# untitled.net
KiCad netlist of a schematic drawn in EAGLE
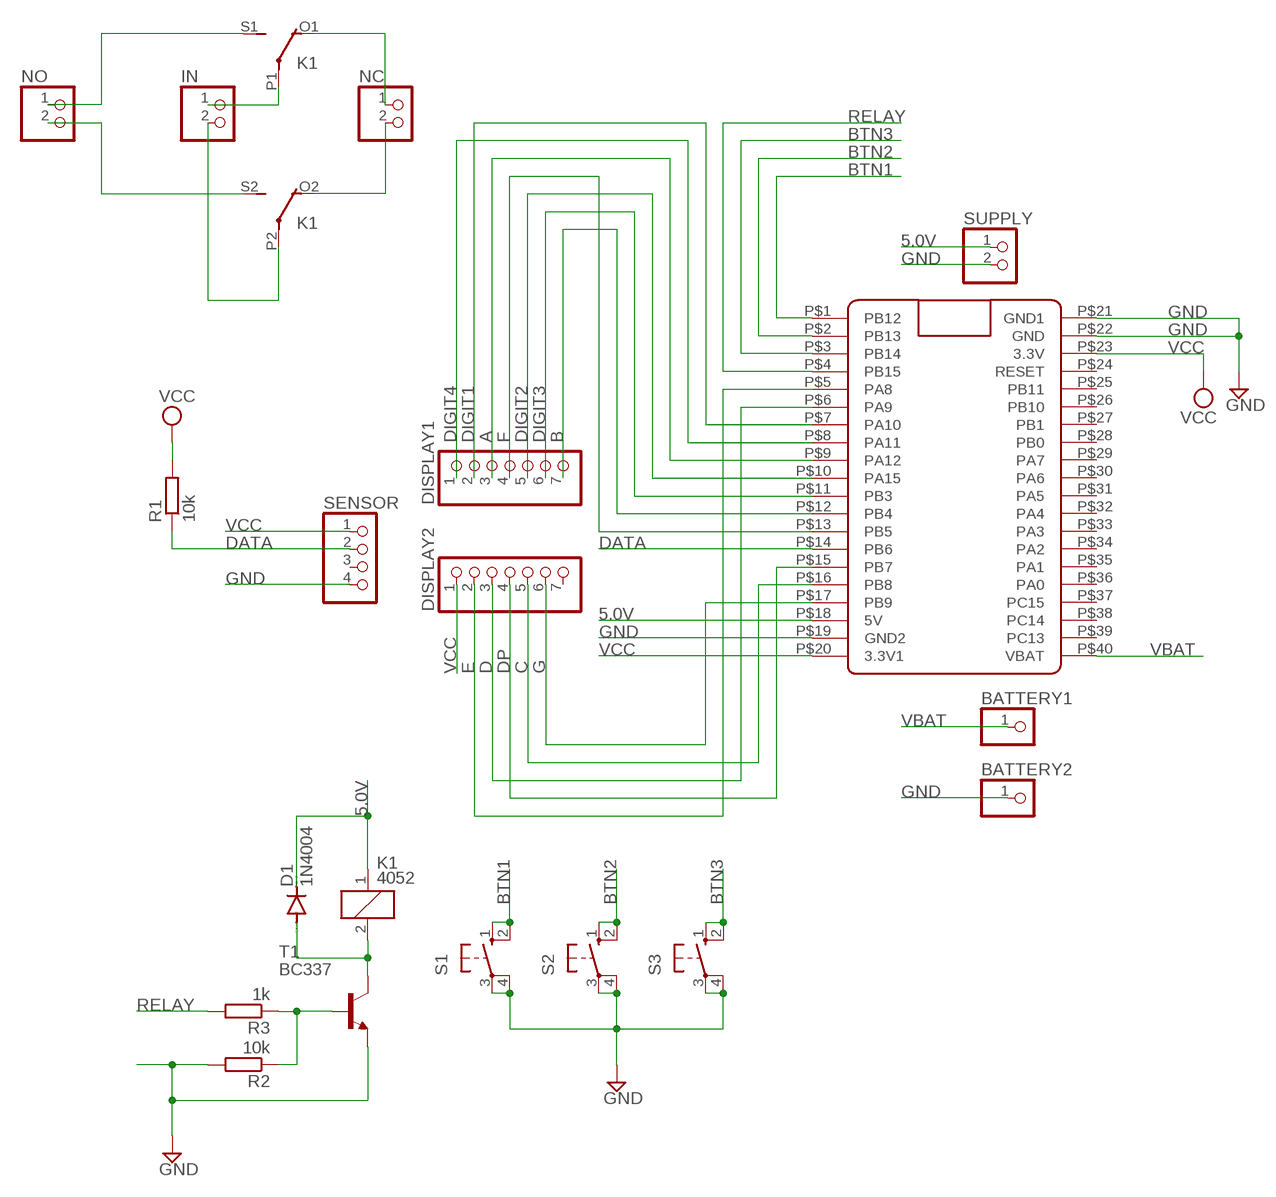
[diagram p0: schematic, sheet 1]

(export (version "E")
  (design (tool "Eeschema 10.0.6"))
  (components
    (comp (ref "BATTERY1")
      (value "PINHD-1X1")
      (footprint "eagle-import:1X01")
      (libsource (lib "eagle-import") (part "PINHD-1X1"))
    )
    (comp (ref "BATTERY2")
      (value "PINHD-1X1")
      (footprint "eagle-import:1X01")
      (libsource (lib "eagle-import") (part "PINHD-1X1"))
    )
    (comp (ref "D1")
      (value "1N4004")
      (footprint "eagle-import:DO41-10")
      (libsource (lib "eagle-import") (part "1N4004"))
    )
    (comp (ref "DISPLAY1")
      (value "PINHD-1X7")
      (footprint "eagle-import:1X07")
      (libsource (lib "eagle-import") (part "PINHD-1X7"))
    )
    (comp (ref "DISPLAY2")
      (value "PINHD-1X7")
      (footprint "eagle-import:1X07")
      (libsource (lib "eagle-import") (part "PINHD-1X7"))
    )
    (comp (ref "IN")
      (value "PINHD-1X2")
      (footprint "eagle-import:1X02")
      (libsource (lib "eagle-import") (part "PINHD-1X2"))
    )
    (comp (ref "K1")
      (value "4052")
      (footprint "eagle-import:F4052")
      (libsource (lib "eagle-import") (part "4052"))
    )
    (comp (ref "NC")
      (value "PINHD-1X2")
      (footprint "eagle-import:1X02")
      (libsource (lib "eagle-import") (part "PINHD-1X2"))
    )
    (comp (ref "NO")
      (value "PINHD-1X2")
      (footprint "eagle-import:1X02")
      (libsource (lib "eagle-import") (part "PINHD-1X2"))
    )
    (comp (ref "R1")
      (value "10k")
      (footprint "eagle-import:0207_10")
      (libsource (lib "eagle-import") (part "R-EU_0207/10"))
    )
    (comp (ref "R2")
      (value "10k")
      (footprint "eagle-import:0207_10")
      (libsource (lib "eagle-import") (part "R-EU_0207/10"))
    )
    (comp (ref "R3")
      (value "1k")
      (footprint "eagle-import:0207_10")
      (libsource (lib "eagle-import") (part "R-EU_0207/10"))
    )
    (comp (ref "S1")
      (value "10-XX")
      (footprint "eagle-import:B3F-10XX")
      (fields (field (name "MPN") "B3F-1000"))
      (libsource (lib "eagle-import") (part "10-XX"))
    )
    (comp (ref "S2")
      (value "10-XX")
      (footprint "eagle-import:B3F-10XX")
      (fields (field (name "MPN") "B3F-1000"))
      (libsource (lib "eagle-import") (part "10-XX"))
    )
    (comp (ref "S3")
      (value "10-XX")
      (footprint "eagle-import:B3F-10XX")
      (fields (field (name "MPN") "B3F-1000"))
      (libsource (lib "eagle-import") (part "10-XX"))
    )
    (comp (ref "SENSOR")
      (value "PINHD-1X4")
      (footprint "eagle-import:1X04")
      (libsource (lib "eagle-import") (part "PINHD-1X4"))
    )
    (comp (ref "SUPPLY")
      (value "PINHD-1X2")
      (footprint "eagle-import:1X02")
      (libsource (lib "eagle-import") (part "PINHD-1X2"))
    )
    (comp (ref "T1")
      (value "BC337")
      (footprint "eagle-import:TO92")
      (libsource (lib "eagle-import") (part "BC337"))
    )
    (comp (ref "U$1")
      (value "BLUE_PILL")
      (footprint "eagle-import:BLUE_PILL")
      (libsource (lib "eagle-import") (part "BLUE_PILL"))
    )
  )
  (nets
    (net (code "1") (name "/5.0V") (class "Default")
      (node (ref "D1") (pin "C") (pinfunction "C_C") (pintype "passive"))
      (node (ref "K1") (pin "1") (pinfunction "1_1") (pintype "passive"))
      (node (ref "SUPPLY") (pin "1") (pinfunction "1_1") (pintype "passive"))
      (node (ref "U$1") (pin "P$18") (pinfunction "5V_P$18") (pintype "bidirectional"))
    )
    (net (code "2") (name "/A") (class "Default")
      (node (ref "DISPLAY1") (pin "3") (pinfunction "3_3") (pintype "passive"))
      (node (ref "U$1") (pin "P$9") (pinfunction "PA12_P$9") (pintype "bidirectional"))
    )
    (net (code "3") (name "/B") (class "Default")
      (node (ref "DISPLAY1") (pin "7") (pinfunction "7_7") (pintype "passive"))
      (node (ref "U$1") (pin "P$12") (pinfunction "PB4_P$12") (pintype "bidirectional"))
    )
    (net (code "4") (name "/BTN1") (class "Default")
      (node (ref "S1") (pin "1") (pinfunction "S_1") (pintype "passive"))
      (node (ref "S1") (pin "2") (pinfunction "S1_2") (pintype "passive"))
      (node (ref "U$1") (pin "P$1") (pinfunction "PB12_P$1") (pintype "bidirectional"))
    )
    (net (code "5") (name "/BTN2") (class "Default")
      (node (ref "S2") (pin "1") (pinfunction "S_1") (pintype "passive"))
      (node (ref "S2") (pin "2") (pinfunction "S1_2") (pintype "passive"))
      (node (ref "U$1") (pin "P$2") (pinfunction "PB13_P$2") (pintype "bidirectional"))
    )
    (net (code "6") (name "/BTN3") (class "Default")
      (node (ref "S3") (pin "1") (pinfunction "S_1") (pintype "passive"))
      (node (ref "S3") (pin "2") (pinfunction "S1_2") (pintype "passive"))
      (node (ref "U$1") (pin "P$3") (pinfunction "PB14_P$3") (pintype "bidirectional"))
    )
    (net (code "7") (name "/C") (class "Default")
      (node (ref "DISPLAY2") (pin "5") (pinfunction "5_5") (pintype "passive"))
      (node (ref "U$1") (pin "P$16") (pinfunction "PB8_P$16") (pintype "bidirectional"))
    )
    (net (code "8") (name "/D") (class "Default")
      (node (ref "DISPLAY2") (pin "3") (pinfunction "3_3") (pintype "passive"))
      (node (ref "U$1") (pin "P$6") (pinfunction "PA9_P$6") (pintype "bidirectional"))
    )
    (net (code "9") (name "/DATA") (class "Default")
      (node (ref "R1") (pin "1") (pinfunction "1_1") (pintype "passive"))
      (node (ref "SENSOR") (pin "2") (pinfunction "2_2") (pintype "passive"))
      (node (ref "U$1") (pin "P$14") (pinfunction "PB6_P$14") (pintype "bidirectional"))
    )
    (net (code "10") (name "/DIGIT1") (class "Default")
      (node (ref "DISPLAY1") (pin "2") (pinfunction "2_2") (pintype "passive"))
      (node (ref "U$1") (pin "P$7") (pinfunction "PA10_P$7") (pintype "bidirectional"))
    )
    (net (code "11") (name "/DIGIT2") (class "Default")
      (node (ref "DISPLAY1") (pin "5") (pinfunction "5_5") (pintype "passive"))
      (node (ref "U$1") (pin "P$10") (pinfunction "PA15_P$10") (pintype "bidirectional"))
    )
    (net (code "12") (name "/DIGIT3") (class "Default")
      (node (ref "DISPLAY1") (pin "6") (pinfunction "6_6") (pintype "passive"))
      (node (ref "U$1") (pin "P$11") (pinfunction "PB3_P$11") (pintype "bidirectional"))
    )
    (net (code "13") (name "/DIGIT4") (class "Default")
      (node (ref "DISPLAY1") (pin "1") (pinfunction "1_1") (pintype "passive"))
      (node (ref "U$1") (pin "P$8") (pinfunction "PA11_P$8") (pintype "bidirectional"))
    )
    (net (code "14") (name "/DP") (class "Default")
      (node (ref "DISPLAY2") (pin "4") (pinfunction "4_4") (pintype "passive"))
      (node (ref "U$1") (pin "P$15") (pinfunction "PB7_P$15") (pintype "bidirectional"))
    )
    (net (code "15") (name "/E") (class "Default")
      (node (ref "DISPLAY2") (pin "2") (pinfunction "2_2") (pintype "passive"))
      (node (ref "U$1") (pin "P$5") (pinfunction "PA8_P$5") (pintype "bidirectional"))
    )
    (net (code "16") (name "/F") (class "Default")
      (node (ref "DISPLAY1") (pin "4") (pinfunction "4_4") (pintype "passive"))
      (node (ref "U$1") (pin "P$13") (pinfunction "PB5_P$13") (pintype "bidirectional"))
    )
    (net (code "17") (name "/G") (class "Default")
      (node (ref "DISPLAY2") (pin "6") (pinfunction "6_6") (pintype "passive"))
      (node (ref "U$1") (pin "P$17") (pinfunction "PB9_P$17") (pintype "bidirectional"))
    )
    (net (code "18") (name "/RELAY") (class "Default")
      (node (ref "R3") (pin "2") (pinfunction "2_2") (pintype "passive"))
      (node (ref "U$1") (pin "P$4") (pinfunction "PB15_P$4") (pintype "bidirectional"))
    )
    (net (code "19") (name "/VBAT") (class "Default")
      (node (ref "BATTERY1") (pin "1") (pinfunction "1_1") (pintype "passive"))
      (node (ref "U$1") (pin "P$40") (pinfunction "VBAT_P$40") (pintype "bidirectional"))
    )
    (net (code "20") (name "GND") (class "Default")
      (node (ref "BATTERY2") (pin "1") (pinfunction "1_1") (pintype "passive"))
      (node (ref "R2") (pin "2") (pinfunction "2_2") (pintype "passive"))
      (node (ref "S1") (pin "3") (pinfunction "P_3") (pintype "passive"))
      (node (ref "S1") (pin "4") (pinfunction "P1_4") (pintype "passive"))
      (node (ref "S2") (pin "3") (pinfunction "P_3") (pintype "passive"))
      (node (ref "S2") (pin "4") (pinfunction "P1_4") (pintype "passive"))
      (node (ref "S3") (pin "3") (pinfunction "P_3") (pintype "passive"))
      (node (ref "S3") (pin "4") (pinfunction "P1_4") (pintype "passive"))
      (node (ref "SENSOR") (pin "4") (pinfunction "4_4") (pintype "passive"))
      (node (ref "SUPPLY") (pin "2") (pinfunction "2_2") (pintype "passive"))
      (node (ref "T1") (pin "1") (pinfunction "E_1") (pintype "passive"))
      (node (ref "U$1") (pin "P$19") (pinfunction "GND2_P$19") (pintype "bidirectional"))
      (node (ref "U$1") (pin "P$21") (pinfunction "GND1_P$21") (pintype "power_in"))
      (node (ref "U$1") (pin "P$22") (pinfunction "GND_P$22") (pintype "bidirectional"))
    )
    (net (code "21") (name "Net-(K1B-O)") (class "Default")
      (node (ref "K1") (pin "O1") (pinfunction "O_O1") (pintype "passive"))
      (node (ref "NC") (pin "1") (pinfunction "1_1") (pintype "passive"))
    )
    (net (code "22") (name "Net-(K1B-P)") (class "Default")
      (node (ref "IN") (pin "1") (pinfunction "1_1") (pintype "passive"))
      (node (ref "K1") (pin "P1") (pinfunction "P_P1") (pintype "passive"))
    )
    (net (code "23") (name "Net-(K1B-S)") (class "Default")
      (node (ref "K1") (pin "S1") (pinfunction "S_S1") (pintype "passive"))
      (node (ref "NO") (pin "1") (pinfunction "1_1") (pintype "passive"))
    )
    (net (code "24") (name "Net-(K1C-O)") (class "Default")
      (node (ref "K1") (pin "O2") (pinfunction "O_O2") (pintype "passive"))
      (node (ref "NC") (pin "2") (pinfunction "2_2") (pintype "passive"))
    )
    (net (code "25") (name "Net-(K1C-P)") (class "Default")
      (node (ref "IN") (pin "2") (pinfunction "2_2") (pintype "passive"))
      (node (ref "K1") (pin "P2") (pinfunction "P_P2") (pintype "passive"))
    )
    (net (code "26") (name "Net-(K1C-S)") (class "Default")
      (node (ref "K1") (pin "S2") (pinfunction "S_S2") (pintype "passive"))
      (node (ref "NO") (pin "2") (pinfunction "2_2") (pintype "passive"))
    )
    (net (code "27") (name "Net-(T1-B)") (class "Default")
      (node (ref "R2") (pin "1") (pinfunction "1_1") (pintype "passive"))
      (node (ref "R3") (pin "1") (pinfunction "1_1") (pintype "passive"))
      (node (ref "T1") (pin "2") (pinfunction "B_2") (pintype "passive"))
    )
    (net (code "28") (name "Net-(T1-C)") (class "Default")
      (node (ref "D1") (pin "A") (pinfunction "A_A") (pintype "passive"))
      (node (ref "K1") (pin "2") (pinfunction "2_2") (pintype "passive"))
      (node (ref "T1") (pin "3") (pinfunction "C_3") (pintype "passive"))
    )
    (net (code "29") (name "VCC") (class "Default")
      (node (ref "DISPLAY2") (pin "1") (pinfunction "1_1") (pintype "passive"))
      (node (ref "R1") (pin "2") (pinfunction "2_2") (pintype "passive"))
      (node (ref "SENSOR") (pin "1") (pinfunction "1_1") (pintype "passive"))
      (node (ref "U$1") (pin "P$20") (pinfunction "3.3V1_P$20") (pintype "bidirectional"))
      (node (ref "U$1") (pin "P$23") (pinfunction "3.3V_P$23") (pintype "bidirectional"))
    )
    (net (code "30") (name "unconnected-(DISPLAY2-Pad7)") (class "Default")
      (node (ref "DISPLAY2") (pin "7") (pinfunction "7_7") (pintype "passive"))
    )
    (net (code "31") (name "unconnected-(SENSOR-Pad3)") (class "Default")
      (node (ref "SENSOR") (pin "3") (pinfunction "3_3") (pintype "passive"))
    )
    (net (code "32") (name "unconnected-(U$1-PA0-PadP$36)") (class "Default")
      (node (ref "U$1") (pin "P$36") (pinfunction "PA0_P$36") (pintype "bidirectional"))
    )
    (net (code "33") (name "unconnected-(U$1-PA1-PadP$35)") (class "Default")
      (node (ref "U$1") (pin "P$35") (pinfunction "PA1_P$35") (pintype "bidirectional"))
    )
    (net (code "34") (name "unconnected-(U$1-PA2-PadP$34)") (class "Default")
      (node (ref "U$1") (pin "P$34") (pinfunction "PA2_P$34") (pintype "bidirectional"))
    )
    (net (code "35") (name "unconnected-(U$1-PA3-PadP$33)") (class "Default")
      (node (ref "U$1") (pin "P$33") (pinfunction "PA3_P$33") (pintype "bidirectional"))
    )
    (net (code "36") (name "unconnected-(U$1-PA4-PadP$32)") (class "Default")
      (node (ref "U$1") (pin "P$32") (pinfunction "PA4_P$32") (pintype "bidirectional"))
    )
    (net (code "37") (name "unconnected-(U$1-PA5-PadP$31)") (class "Default")
      (node (ref "U$1") (pin "P$31") (pinfunction "PA5_P$31") (pintype "bidirectional"))
    )
    (net (code "38") (name "unconnected-(U$1-PA6-PadP$30)") (class "Default")
      (node (ref "U$1") (pin "P$30") (pinfunction "PA6_P$30") (pintype "bidirectional"))
    )
    (net (code "39") (name "unconnected-(U$1-PA7-PadP$29)") (class "Default")
      (node (ref "U$1") (pin "P$29") (pinfunction "PA7_P$29") (pintype "bidirectional"))
    )
    (net (code "40") (name "unconnected-(U$1-PB0-PadP$28)") (class "Default")
      (node (ref "U$1") (pin "P$28") (pinfunction "PB0_P$28") (pintype "bidirectional"))
    )
    (net (code "41") (name "unconnected-(U$1-PB1-PadP$27)") (class "Default")
      (node (ref "U$1") (pin "P$27") (pinfunction "PB1_P$27") (pintype "bidirectional"))
    )
    (net (code "42") (name "unconnected-(U$1-PB10-PadP$26)") (class "Default")
      (node (ref "U$1") (pin "P$26") (pinfunction "PB10_P$26") (pintype "bidirectional"))
    )
    (net (code "43") (name "unconnected-(U$1-PB11-PadP$25)") (class "Default")
      (node (ref "U$1") (pin "P$25") (pinfunction "PB11_P$25") (pintype "bidirectional"))
    )
    (net (code "44") (name "unconnected-(U$1-PC13-PadP$39)") (class "Default")
      (node (ref "U$1") (pin "P$39") (pinfunction "PC13_P$39") (pintype "bidirectional"))
    )
    (net (code "45") (name "unconnected-(U$1-PC14-PadP$38)") (class "Default")
      (node (ref "U$1") (pin "P$38") (pinfunction "PC14_P$38") (pintype "bidirectional"))
    )
    (net (code "46") (name "unconnected-(U$1-PC15-PadP$37)") (class "Default")
      (node (ref "U$1") (pin "P$37") (pinfunction "PC15_P$37") (pintype "bidirectional"))
    )
    (net (code "47") (name "unconnected-(U$1-RESET-PadP$24)") (class "Default")
      (node (ref "U$1") (pin "P$24") (pinfunction "RESET_P$24") (pintype "bidirectional"))
    )
  )
)
